# My_CryStal.net
KiCad netlist of a schematic drawn in Altium Designer
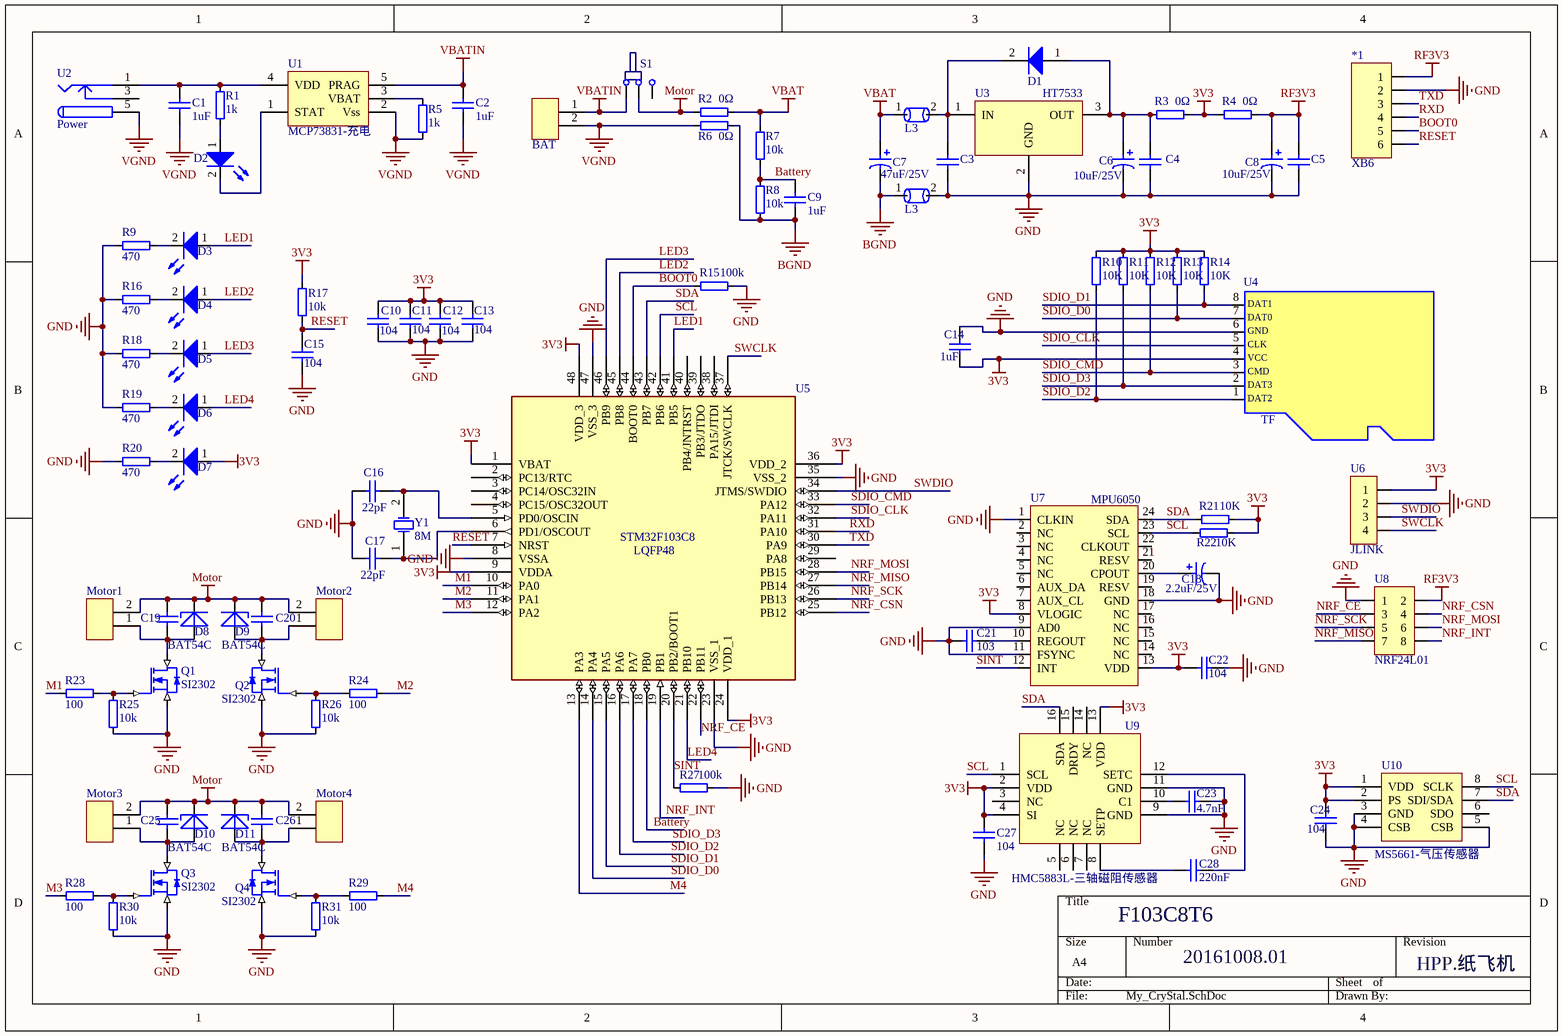
[diagram p0: My_CryStal.SchDoc]

(export (version "E")
  (design (tool "Eeschema 10.0.6"))
  (components
    (comp (ref "*1") (value "XB6") (footprint "SIP6") (libsource (lib "My_Sheet-All_STM32") (part "XB6")))
    (comp (ref "*2") (value "L3") (footprint "2010") (libsource (lib "My_Sheet-All_STM32") (part "L3")))
    (comp (ref "*3") (value "L3") (footprint "2010") (libsource (lib "My_Sheet-All_STM32") (part "L3")))
    (comp (ref "C1")
      (value "1uF")
      (footprint "0805 - duplicate")
      (description "0805")
      (fields (field (name "TOLERANCE") "10%"))
      (libsource (lib "My_Sheet-All_STM32") (part "CAP SMD 0603  X5R 1µF 25V 10%"))
    )
    (comp (ref "C2")
      (value "1uF")
      (footprint "0805 - duplicate")
      (description "0805")
      (fields (field (name "TOLERANCE") "10%"))
      (libsource (lib "My_Sheet-All_STM32") (part "CAP SMD 0603  X5R 1µF 25V 10%"))
    )
    (comp (ref "C3")
      (value "104")
      (footprint "0805 - duplicate")
      (description "0805")
      (fields (field (name "PUBLISHER") "Altium Limited"))
      (libsource (lib "My_Sheet-All_STM32") (part "C1"))
    )
    (comp (ref "C4")
      (value "104")
      (footprint "0805 - duplicate")
      (description "0805")
      (fields (field (name "PUBLISHER") "Altium Limited"))
      (libsource (lib "My_Sheet-All_STM32") (part "C1"))
    )
    (comp (ref "C5")
      (value "104")
      (footprint "0805 - duplicate")
      (description "0805")
      (fields (field (name "PUBLISHER") "Altium Limited"))
      (libsource (lib "My_Sheet-All_STM32") (part "C1"))
    )
    (comp (ref "C6")
      (value "10uF/25V")
      (footprint "1206")
      (description "0805")
      (fields (field (name "PUBLISHER") "Altium Limited"))
      (libsource (lib "My_Sheet-All_STM32") (part "Cap Pol"))
    )
    (comp (ref "C7")
      (value "47uF/25V")
      (footprint "1206")
      (description "0805")
      (fields (field (name "PUBLISHER") "Altium Limited"))
      (libsource (lib "My_Sheet-All_STM32") (part "Cap Pol"))
    )
    (comp (ref "C8")
      (value "10uF/25V")
      (footprint "1206")
      (description "0805")
      (fields (field (name "PUBLISHER") "Altium Limited"))
      (libsource (lib "My_Sheet-All_STM32") (part "Cap Pol"))
    )
    (comp (ref "C9")
      (value "1uF")
      (footprint "0805 - duplicate")
      (description "0805")
      (fields (field (name "TOLERANCE") "10%"))
      (libsource (lib "My_Sheet-All_STM32") (part "CAP SMD 0603  X5R 1µF 25V 10%"))
    )
    (comp (ref "C10")
      (value "104")
      (footprint "0805 - duplicate")
      (description "Cap")
      (fields (field (name "PUBLISHER") "Altium Limited"))
      (libsource (lib "My_Sheet-All_STM32") (part "C1"))
    )
    (comp (ref "C11")
      (value "104")
      (footprint "0805 - duplicate")
      (description "Cap")
      (fields (field (name "PUBLISHER") "Altium Limited"))
      (libsource (lib "My_Sheet-All_STM32") (part "C1"))
    )
    (comp (ref "C12")
      (value "104")
      (footprint "0805 - duplicate")
      (description "Cap")
      (fields (field (name "PUBLISHER") "Altium Limited"))
      (libsource (lib "My_Sheet-All_STM32") (part "C1"))
    )
    (comp (ref "C13")
      (value "104")
      (footprint "0805 - duplicate")
      (description "Cap")
      (fields (field (name "PUBLISHER") "Altium Limited"))
      (libsource (lib "My_Sheet-All_STM32") (part "C1"))
    )
    (comp (ref "C14")
      (value "1uF")
      (footprint "0805 - duplicate")
      (description "0805")
      (fields (field (name "TOLERANCE") "10%"))
      (libsource (lib "My_Sheet-All_STM32") (part "CAP SMD 0603  X5R 1µF 25V 10%"))
    )
    (comp (ref "C15")
      (value "104")
      (footprint "0805 - duplicate")
      (description "Cap")
      (fields (field (name "PUBLISHER") "Altium Limited"))
      (libsource (lib "My_Sheet-All_STM32") (part "C1"))
    )
    (comp (ref "C16")
      (value "22pF")
      (footprint "0805 - duplicate")
      (description "Capacitor")
      (fields (field (name "Comment") "Cap") (field (name "PUBLISHER") "Altium Limited"))
      (libsource (lib "Miscellaneous Devices") (part "Cap"))
    )
    (comp (ref "C17")
      (value "22pF")
      (footprint "0805 - duplicate")
      (description "Capacitor")
      (fields (field (name "Comment") "Cap") (field (name "PUBLISHER") "Altium Limited"))
      (libsource (lib "Miscellaneous Devices") (part "Cap"))
    )
    (comp (ref "C18")
      (value "2.2uF/25V")
      (footprint "1206")
      (description "0805")
      (fields (field (name "PUBLISHER") "Altium Limited"))
      (libsource (lib "") (part "Cap Pol_1"))
    )
    (comp (ref "C19")
      (value "104")
      (footprint "0805 - duplicate")
      (description "Cap")
      (fields (field (name "PUBLISHER") "Altium Limited"))
      (libsource (lib "My_Sheet-All_STM32") (part "C1"))
    )
    (comp (ref "C20")
      (value "104")
      (footprint "0805 - duplicate")
      (description "Cap")
      (fields (field (name "PUBLISHER") "Altium Limited"))
      (libsource (lib "My_Sheet-All_STM32") (part "C1"))
    )
    (comp (ref "C21")
      (value "103")
      (footprint "0805 - duplicate")
      (description "0805")
      (fields (field (name "TOLERANCE") "10%"))
      (libsource (lib "My_Sheet-All_STM32") (part "CAP SMD 0603  X5R 1µF 25V 10%"))
    )
    (comp (ref "C22")
      (value "104")
      (footprint "0805 - duplicate")
      (description "0805")
      (fields (field (name "TOLERANCE") "10%"))
      (libsource (lib "My_Sheet-All_STM32") (part "CAP SMD 0603  X5R 1µF 25V 10%"))
    )
    (comp (ref "C23")
      (value "4.7nF")
      (footprint "0805 - duplicate")
      (description "0805")
      (fields (field (name "TOLERANCE") "10%"))
      (libsource (lib "My_Sheet-All_STM32") (part "CAP SMD 0603  X5R 1µF 25V 10%"))
    )
    (comp (ref "C24")
      (value "104")
      (footprint "0805 - duplicate")
      (description "0805")
      (fields (field (name "TOLERANCE") "10%"))
      (libsource (lib "My_Sheet-All_STM32") (part "CAP SMD 0603  X5R 1µF 25V 10%"))
    )
    (comp (ref "C25")
      (value "104")
      (footprint "0805 - duplicate")
      (description "Cap")
      (fields (field (name "PUBLISHER") "Altium Limited"))
      (libsource (lib "My_Sheet-All_STM32") (part "C1"))
    )
    (comp (ref "C26")
      (value "104")
      (footprint "0805 - duplicate")
      (description "Cap")
      (fields (field (name "PUBLISHER") "Altium Limited"))
      (libsource (lib "My_Sheet-All_STM32") (part "C1"))
    )
    (comp (ref "C27")
      (value "104")
      (footprint "0805 - duplicate")
      (description "0805")
      (fields (field (name "TOLERANCE") "10%"))
      (libsource (lib "My_Sheet-All_STM32") (part "CAP SMD 0603  X5R 1µF 25V 10%"))
    )
    (comp (ref "C28")
      (value "220nF")
      (footprint "0805 - duplicate")
      (description "0805")
      (fields (field (name "TOLERANCE") "10%"))
      (libsource (lib "My_Sheet-All_STM32") (part "CAP SMD 0603  X5R 1µF 25V 10%"))
    )
    (comp (ref "CON1") (value "BAT") (footprint "SIP2") (libsource (lib "") (part "CON2_2")))
    (comp (ref "CON2")
      (value "Motor1")
      (footprint "SIP2")
      (libsource (lib "My_Sheet-All_STM32") (part "CON2"))
    )
    (comp (ref "CON3") (value "Motor2") (footprint "SIP2") (libsource (lib "") (part "CON2_1")))
    (comp (ref "CON4")
      (value "Motor3")
      (footprint "SIP2")
      (libsource (lib "My_Sheet-All_STM32") (part "CON2"))
    )
    (comp (ref "CON5") (value "Motor4") (footprint "SIP2") (libsource (lib "") (part "CON2_1")))
    (comp (ref "D1")
      (value "Diode")
      (footprint "DIODE-SMB")
      (description "整流二极管")
      (fields (field (name "PUBLISHER") "Altium Limited"))
      (libsource (lib "My_Sheet-All_STM32") (part "Diode"))
    )
    (comp (ref "D2")
      (value "LED")
      (footprint "LED")
      (description "发光二极管")
      (fields (field (name "PUBLISHER") "Altium Limited"))
      (libsource (lib "My_Sheet-All_STM32") (part "LED"))
    )
    (comp (ref "D3")
      (value "LED")
      (footprint "LED")
      (description "发光二极管")
      (fields (field (name "PUBLISHER") "Altium Limited"))
      (libsource (lib "My_Sheet-All_STM32") (part "LED"))
    )
    (comp (ref "D4")
      (value "LED")
      (footprint "LED")
      (description "发光二极管")
      (fields (field (name "PUBLISHER") "Altium Limited"))
      (libsource (lib "My_Sheet-All_STM32") (part "LED"))
    )
    (comp (ref "D5")
      (value "LED")
      (footprint "LED")
      (description "发光二极管")
      (fields (field (name "PUBLISHER") "Altium Limited"))
      (libsource (lib "My_Sheet-All_STM32") (part "LED"))
    )
    (comp (ref "D6")
      (value "LED")
      (footprint "LED")
      (description "发光二极管")
      (fields (field (name "PUBLISHER") "Altium Limited"))
      (libsource (lib "My_Sheet-All_STM32") (part "LED"))
    )
    (comp (ref "D7")
      (value "LED")
      (footprint "LED")
      (description "发光二极管")
      (fields (field (name "PUBLISHER") "Altium Limited"))
      (libsource (lib "My_Sheet-All_STM32") (part "LED"))
    )
    (comp (ref "D8")
      (value "BAT54C")
      (footprint "DIODE-SMB")
      (libsource (lib "My_Sheet-All_STM32") (part "TVS"))
    )
    (comp (ref "D9")
      (value "BAT54C")
      (footprint "DIODE-SMB")
      (libsource (lib "My_Sheet-All_STM32") (part "TVS"))
    )
    (comp (ref "D10")
      (value "BAT54C")
      (footprint "DIODE-SMB")
      (libsource (lib "My_Sheet-All_STM32") (part "TVS"))
    )
    (comp (ref "D11")
      (value "BAT54C")
      (footprint "DIODE-SMB")
      (libsource (lib "My_Sheet-All_STM32") (part "TVS"))
    )
    (comp (ref "Q1")
      (value "SI2302")
      (footprint "SOT-23")
      (description "N-Channel MOSFET")
      (libsource (lib "My_Sheet-All_STM32") (part "IRF740"))
    )
    (comp (ref "Q2")
      (value "SI2302")
      (footprint "SOT-23")
      (description "N-Channel MOSFET")
      (libsource (lib "My_Sheet-All_STM32") (part "IRF740"))
    )
    (comp (ref "Q3")
      (value "SI2302")
      (footprint "SOT-23")
      (description "N-Channel MOSFET")
      (libsource (lib "My_Sheet-All_STM32") (part "IRF740"))
    )
    (comp (ref "Q4")
      (value "SI2302")
      (footprint "SOT-23")
      (description "N-Channel MOSFET")
      (libsource (lib "My_Sheet-All_STM32") (part "IRF740"))
    )
    (comp (ref "R1")
      (value "1k")
      (footprint "0805 - duplicate")
      (libsource (lib "My_Sheet-All_STM32") (part "RES_1"))
    )
    (comp (ref "R2")
      (value "0Ω")
      (footprint "0805 - duplicate")
      (libsource (lib "My_Sheet-All_STM32") (part "RES_1"))
    )
    (comp (ref "R3")
      (value "0Ω")
      (footprint "0805 - duplicate")
      (libsource (lib "My_Sheet-All_STM32") (part "RES_1"))
    )
    (comp (ref "R4")
      (value "0Ω")
      (footprint "0805 - duplicate")
      (libsource (lib "My_Sheet-All_STM32") (part "RES_1"))
    )
    (comp (ref "R5")
      (value "1k")
      (footprint "0805 - duplicate")
      (libsource (lib "My_Sheet-All_STM32") (part "RES_1"))
    )
    (comp (ref "R6")
      (value "0Ω")
      (footprint "0805 - duplicate")
      (libsource (lib "My_Sheet-All_STM32") (part "RES_1"))
    )
    (comp (ref "R7")
      (value "10k")
      (footprint "0805 - duplicate")
      (libsource (lib "My_Sheet-All_STM32") (part "RES_1"))
    )
    (comp (ref "R8")
      (value "10k")
      (footprint "0805 - duplicate")
      (libsource (lib "My_Sheet-All_STM32") (part "RES_1"))
    )
    (comp (ref "R9")
      (value "470")
      (footprint "0805 - duplicate")
      (libsource (lib "My_Sheet-All_STM32") (part "RES_1"))
    )
    (comp (ref "R10")
      (value "10K")
      (footprint "0805 - duplicate")
      (libsource (lib "My_Sheet-All_STM32") (part "RES_1"))
    )
    (comp (ref "R11")
      (value "10K")
      (footprint "0805 - duplicate")
      (libsource (lib "My_Sheet-All_STM32") (part "RES_1"))
    )
    (comp (ref "R12")
      (value "10K")
      (footprint "0805 - duplicate")
      (libsource (lib "My_Sheet-All_STM32") (part "RES_1"))
    )
    (comp (ref "R13")
      (value "10K")
      (footprint "0805 - duplicate")
      (libsource (lib "My_Sheet-All_STM32") (part "RES_1"))
    )
    (comp (ref "R14")
      (value "10K")
      (footprint "0805 - duplicate")
      (libsource (lib "My_Sheet-All_STM32") (part "RES_1"))
    )
    (comp (ref "R15")
      (value "100k")
      (footprint "0805 - duplicate")
      (libsource (lib "My_Sheet-All_STM32") (part "RES_1"))
    )
    (comp (ref "R16")
      (value "470")
      (footprint "0805 - duplicate")
      (libsource (lib "My_Sheet-All_STM32") (part "RES_1"))
    )
    (comp (ref "R17")
      (value "10k")
      (footprint "0805 - duplicate")
      (libsource (lib "My_Sheet-All_STM32") (part "RES_1"))
    )
    (comp (ref "R18")
      (value "470")
      (footprint "0805 - duplicate")
      (libsource (lib "My_Sheet-All_STM32") (part "RES_1"))
    )
    (comp (ref "R19")
      (value "470")
      (footprint "0805 - duplicate")
      (libsource (lib "My_Sheet-All_STM32") (part "RES_1"))
    )
    (comp (ref "R20")
      (value "470")
      (footprint "0805 - duplicate")
      (libsource (lib "My_Sheet-All_STM32") (part "RES_1"))
    )
    (comp (ref "R21")
      (value "10K")
      (footprint "0805 - duplicate")
      (libsource (lib "My_Sheet-All_STM32") (part "RES_1"))
    )
    (comp (ref "R22")
      (value "10K")
      (footprint "0805 - duplicate")
      (libsource (lib "My_Sheet-All_STM32") (part "RES_1"))
    )
    (comp (ref "R23")
      (value "100")
      (footprint "0805 - duplicate")
      (libsource (lib "My_Sheet-All_STM32") (part "RES_1"))
    )
    (comp (ref "R24")
      (value "100")
      (footprint "0805 - duplicate")
      (libsource (lib "My_Sheet-All_STM32") (part "RES_1"))
    )
    (comp (ref "R25")
      (value "10k")
      (footprint "0805 - duplicate")
      (libsource (lib "My_Sheet-All_STM32") (part "RES_1"))
    )
    (comp (ref "R26")
      (value "10k")
      (footprint "0805 - duplicate")
      (libsource (lib "My_Sheet-All_STM32") (part "RES_1"))
    )
    (comp (ref "R27")
      (value "100k")
      (footprint "0805 - duplicate")
      (libsource (lib "My_Sheet-All_STM32") (part "RES_1"))
    )
    (comp (ref "R28")
      (value "100")
      (footprint "0805 - duplicate")
      (libsource (lib "My_Sheet-All_STM32") (part "RES_1"))
    )
    (comp (ref "R29")
      (value "100")
      (footprint "0805 - duplicate")
      (libsource (lib "My_Sheet-All_STM32") (part "RES_1"))
    )
    (comp (ref "R30")
      (value "10k")
      (footprint "0805 - duplicate")
      (libsource (lib "My_Sheet-All_STM32") (part "RES_1"))
    )
    (comp (ref "R31")
      (value "10k")
      (footprint "0805 - duplicate")
      (libsource (lib "My_Sheet-All_STM32") (part "RES_1"))
    )
    (comp (ref "S1") (value "SW") (footprint "SWITCH_B1") (libsource (lib "My_Sheet-All_STM32") (part "SW")))
    (comp (ref "U1")
      (value "MCP73831-充电")
      (footprint "SOT23-5")
      (libsource (lib "My_Sheet-All_STM32") (part "MCP73831"))
    )
    (comp (ref "U2") (value "Power") (footprint "USB5") (libsource (lib "My_Sheet-All_STM32") (part "Power")))
    (comp (ref "U3")
      (value "HT7533")
      (footprint "SOT-89")
      (libsource (lib "My_Sheet-All_STM32") (part "HT7533"))
    )
    (comp (ref "U4") (value "TF") (footprint "SDCARD_L") (libsource (lib "My_Sheet-All_STM32") (part "TF")))
    (comp (ref "U5")
      (value "STM32F103C8T6-1")
      (footprint "LQFP48S")
      (description "Medium-density performance line ARM-based 32-bit MCU with 64KB Flash, USB, CAN, 7 timers, 2 ADCs")
      (libsource (lib "My_Sheet-All_STM32") (part "STM32F103C8T6-1"))
    )
    (comp (ref "U6") (value "JLINK") (footprint "SIP4") (libsource (lib "My_Sheet-All_STM32") (part "X4")))
    (comp (ref "U7")
      (value "MPU6050")
      (footprint "QFN24")
      (libsource (lib "My_Sheet-All_STM32") (part "MPU6050"))
    )
    (comp (ref "U8")
      (value "NRF24L01")
      (footprint "DIP8")
      (description "Header, 6-Pin")
      (fields (field (name "PUBLISHER") "*"))
      (libsource (lib "My_Sheet-All_STM32") (part "Header 4X2"))
    )
    (comp (ref "U9")
      (value "HMC5883L-三轴磁阻传感器")
      (footprint "LCC16")
      (libsource (lib "My_Sheet-All_STM32") (part "HMC5883L"))
    )
    (comp (ref "U10")
      (value "MS5661-气压传感器")
      (footprint "LCC8")
      (libsource (lib "My_Sheet-All_STM32") (part "MS5611"))
    )
    (comp (ref "Y1")
      (value "8M")
      (footprint "XTAL")
      (description "Crystal Oscillator")
      (fields (field (name "PUBLISHER") "Altium Limited"))
      (libsource (lib "Miscellaneous Devices") (part "XTAL"))
    )
  )
  (nets
    (net (code "1") (name "/BOOT0") (class "Default")
      (node (ref "*1") (pin "5") (pinfunction "5_5") (pintype "passive"))
      (node (ref "R15") (pin "2") (pinfunction "2_2") (pintype "passive"))
      (node (ref "U5") (pin "44") (pinfunction "BOOT0_44") (pintype "bidirectional"))
    )
    (net (code "2") (name "/Battery") (class "Default")
      (node (ref "C9") (pin "2") (pinfunction "2_2") (pintype "passive"))
      (node (ref "R7") (pin "1") (pinfunction "1_1") (pintype "passive"))
      (node (ref "R8") (pin "2") (pinfunction "2_2") (pintype "passive"))
      (node (ref "U5") (pin "18") (pinfunction "PB0_18") (pintype "bidirectional"))
    )
    (net (code "3") (name "/LED1") (class "Default")
      (node (ref "D3") (pin "1") (pinfunction "A_1") (pintype "passive"))
      (node (ref "U5") (pin "41") (pinfunction "PB5_41") (pintype "bidirectional"))
    )
    (net (code "4") (name "/LED2") (class "Default")
      (node (ref "D4") (pin "1") (pinfunction "A_1") (pintype "passive"))
      (node (ref "U5") (pin "45") (pinfunction "PB8_45") (pintype "bidirectional"))
    )
    (net (code "5") (name "/LED3") (class "Default")
      (node (ref "D5") (pin "1") (pinfunction "A_1") (pintype "passive"))
      (node (ref "U5") (pin "46") (pinfunction "PB9_46") (pintype "bidirectional"))
    )
    (net (code "6") (name "/LED4") (class "Default")
      (node (ref "D6") (pin "1") (pinfunction "A_1") (pintype "passive"))
      (node (ref "U5") (pin "21") (pinfunction "PB10_21") (pintype "bidirectional"))
    )
    (net (code "7") (name "/M1") (class "Default")
      (node (ref "R23") (pin "1") (pinfunction "1_1") (pintype "passive"))
      (node (ref "U5") (pin "10") (pinfunction "PA0_10") (pintype "bidirectional"))
    )
    (net (code "8") (name "/M2") (class "Default")
      (node (ref "R24") (pin "1") (pinfunction "1_1") (pintype "passive"))
      (node (ref "U5") (pin "11") (pinfunction "PA1_11") (pintype "bidirectional"))
    )
    (net (code "9") (name "/M3") (class "Default")
      (node (ref "R28") (pin "1") (pinfunction "1_1") (pintype "passive"))
      (node (ref "U5") (pin "12") (pinfunction "PA2_12") (pintype "bidirectional"))
    )
    (net (code "10") (name "/M4") (class "Default")
      (node (ref "R29") (pin "1") (pinfunction "1_1") (pintype "passive"))
      (node (ref "U5") (pin "13") (pinfunction "PA3_13") (pintype "bidirectional"))
    )
    (net (code "11") (name "/NRF_CE") (class "Default")
      (node (ref "U5") (pin "22") (pinfunction "PB11_22") (pintype "bidirectional"))
      (node (ref "U8") (pin "3") (pinfunction "3_3") (pintype "passive"))
    )
    (net (code "12") (name "/NRF_CSN") (class "Default")
      (node (ref "U5") (pin "25") (pinfunction "PB12_25") (pintype "bidirectional"))
      (node (ref "U8") (pin "4") (pinfunction "4_4") (pintype "passive"))
    )
    (net (code "13") (name "/NRF_INT") (class "Default")
      (node (ref "U5") (pin "19") (pinfunction "PB1_19") (pintype "input"))
      (node (ref "U8") (pin "8") (pinfunction "8_8") (pintype "passive"))
    )
    (net (code "14") (name "/NRF_MISO") (class "Default")
      (node (ref "U5") (pin "27") (pinfunction "PB14_27") (pintype "bidirectional"))
      (node (ref "U8") (pin "7") (pinfunction "7_7") (pintype "passive"))
    )
    (net (code "15") (name "/NRF_MOSI") (class "Default")
      (node (ref "U5") (pin "28") (pinfunction "PB15_28") (pintype "bidirectional"))
      (node (ref "U8") (pin "6") (pinfunction "6_6") (pintype "passive"))
    )
    (net (code "16") (name "/NRF_SCK") (class "Default")
      (node (ref "U5") (pin "26") (pinfunction "PB13_26") (pintype "bidirectional"))
      (node (ref "U8") (pin "5") (pinfunction "5_5") (pintype "passive"))
    )
    (net (code "17") (name "/RESET") (class "Default")
      (node (ref "*1") (pin "6") (pinfunction "6_6") (pintype "passive"))
      (node (ref "C15") (pin "2") (pinfunction "2_2") (pintype "passive"))
      (node (ref "R17") (pin "1") (pinfunction "1_1") (pintype "passive"))
      (node (ref "U5") (pin "7") (pinfunction "NRST_7") (pintype "input"))
    )
    (net (code "18") (name "/RXD") (class "Default")
      (node (ref "*1") (pin "4") (pinfunction "4_4") (pintype "passive"))
      (node (ref "U5") (pin "31") (pinfunction "PA10_31") (pintype "bidirectional"))
    )
    (net (code "19") (name "/SCL") (class "Default")
      (node (ref "R22") (pin "2") (pinfunction "2_2") (pintype "passive"))
      (node (ref "U10") (pin "8") (pinfunction "SCLK_8") (pintype "passive"))
      (node (ref "U5") (pin "42") (pinfunction "PB6_42") (pintype "bidirectional"))
      (node (ref "U7") (pin "23") (pinfunction "SCL_23") (pintype "passive"))
      (node (ref "U9") (pin "1") (pinfunction "SCL_1") (pintype "passive"))
    )
    (net (code "20") (name "/SDA") (class "Default")
      (node (ref "R21") (pin "2") (pinfunction "2_2") (pintype "passive"))
      (node (ref "U10") (pin "7") (pinfunction "SDI/SDA_7") (pintype "passive"))
      (node (ref "U5") (pin "43") (pinfunction "PB7_43") (pintype "bidirectional"))
      (node (ref "U7") (pin "24") (pinfunction "SDA_24") (pintype "passive"))
      (node (ref "U9") (pin "16") (pinfunction "SDA_16") (pintype "passive"))
    )
    (net (code "21") (name "/SDIO_CLK") (class "Default")
      (node (ref "U4") (pin "5") (pinfunction "5_5") (pintype "passive"))
      (node (ref "U5") (pin "32") (pinfunction "PA11_32") (pintype "bidirectional"))
    )
    (net (code "22") (name "/SDIO_CMD") (class "Default")
      (node (ref "R12") (pin "2") (pinfunction "2_2") (pintype "passive"))
      (node (ref "U4") (pin "3") (pinfunction "3_3") (pintype "passive"))
      (node (ref "U5") (pin "33") (pinfunction "PA12_33") (pintype "bidirectional"))
    )
    (net (code "23") (name "/SDIO_D0") (class "Default")
      (node (ref "R13") (pin "2") (pinfunction "2_2") (pintype "passive"))
      (node (ref "U4") (pin "7") (pinfunction "7_7") (pintype "passive"))
      (node (ref "U5") (pin "14") (pinfunction "PA4_14") (pintype "bidirectional"))
    )
    (net (code "24") (name "/SDIO_D1") (class "Default")
      (node (ref "R14") (pin "2") (pinfunction "2_2") (pintype "passive"))
      (node (ref "U4") (pin "8") (pinfunction "8_8") (pintype "passive"))
      (node (ref "U5") (pin "15") (pinfunction "PA5_15") (pintype "bidirectional"))
    )
    (net (code "25") (name "/SDIO_D2") (class "Default")
      (node (ref "R10") (pin "2") (pinfunction "2_2") (pintype "passive"))
      (node (ref "U4") (pin "1") (pinfunction "1_1") (pintype "passive"))
      (node (ref "U5") (pin "16") (pinfunction "PA6_16") (pintype "bidirectional"))
    )
    (net (code "26") (name "/SDIO_D3") (class "Default")
      (node (ref "R11") (pin "2") (pinfunction "2_2") (pintype "passive"))
      (node (ref "U4") (pin "2") (pinfunction "2_2") (pintype "passive"))
      (node (ref "U5") (pin "17") (pinfunction "PA7_17") (pintype "bidirectional"))
    )
    (net (code "27") (name "/SINT") (class "Default")
      (node (ref "R27") (pin "2") (pinfunction "2_2") (pintype "passive"))
      (node (ref "U5") (pin "20") (pinfunction "PB2/BOOT1_20") (pintype "bidirectional"))
      (node (ref "U7") (pin "12") (pinfunction "INT_12") (pintype "passive"))
    )
    (net (code "28") (name "/SWCLK") (class "Default")
      (node (ref "U5") (pin "37") (pinfunction "JTCK/SWCLK_37") (pintype "bidirectional"))
      (node (ref "U6") (pin "4") (pinfunction "4_4") (pintype "passive"))
    )
    (net (code "29") (name "/SWDIO") (class "Default")
      (node (ref "U5") (pin "34") (pinfunction "JTMS/SWDIO_34") (pintype "bidirectional"))
      (node (ref "U6") (pin "3") (pinfunction "3_3") (pintype "passive"))
    )
    (net (code "30") (name "/TXD") (class "Default")
      (node (ref "*1") (pin "3") (pinfunction "3_3") (pintype "passive"))
      (node (ref "U5") (pin "30") (pinfunction "PA9_30") (pintype "bidirectional"))
    )
    (net (code "31") (name "3V3") (class "Default")
      (node (ref "C10") (pin "2") (pinfunction "2_2") (pintype "passive"))
      (node (ref "C11") (pin "2") (pinfunction "2_2") (pintype "passive"))
      (node (ref "C12") (pin "2") (pinfunction "2_2") (pintype "passive"))
      (node (ref "C13") (pin "2") (pinfunction "2_2") (pintype "passive"))
      (node (ref "C14") (pin "1") (pinfunction "1_1") (pintype "passive"))
      (node (ref "C22") (pin "1") (pinfunction "1_1") (pintype "passive"))
      (node (ref "C24") (pin "1") (pinfunction "1_1") (pintype "passive"))
      (node (ref "C27") (pin "1") (pinfunction "1_1") (pintype "passive"))
      (node (ref "D7") (pin "1") (pinfunction "A_1") (pintype "passive"))
      (node (ref "R10") (pin "1") (pinfunction "1_1") (pintype "passive"))
      (node (ref "R11") (pin "1") (pinfunction "1_1") (pintype "passive"))
      (node (ref "R12") (pin "1") (pinfunction "1_1") (pintype "passive"))
      (node (ref "R13") (pin "1") (pinfunction "1_1") (pintype "passive"))
      (node (ref "R14") (pin "1") (pinfunction "1_1") (pintype "passive"))
      (node (ref "R17") (pin "2") (pinfunction "2_2") (pintype "passive"))
      (node (ref "R21") (pin "1") (pinfunction "1_1") (pintype "passive"))
      (node (ref "R22") (pin "1") (pinfunction "1_1") (pintype "passive"))
      (node (ref "R3") (pin "1") (pinfunction "1_1") (pintype "passive"))
      (node (ref "R4") (pin "2") (pinfunction "2_2") (pintype "passive"))
      (node (ref "U10") (pin "1") (pinfunction "VDD_1") (pintype "passive"))
      (node (ref "U10") (pin "2") (pinfunction "PS_2") (pintype "passive"))
      (node (ref "U4") (pin "4") (pinfunction "4_4") (pintype "passive"))
      (node (ref "U5") (pin "1") (pinfunction "VBAT_1") (pintype "power_in"))
      (node (ref "U5") (pin "24") (pinfunction "VDD_1_24") (pintype "power_in"))
      (node (ref "U5") (pin "36") (pinfunction "VDD_2_36") (pintype "power_in"))
      (node (ref "U5") (pin "48") (pinfunction "VDD_3_48") (pintype "power_in"))
      (node (ref "U5") (pin "9") (pinfunction "VDDA_9") (pintype "power_in"))
      (node (ref "U6") (pin "1") (pinfunction "1_1") (pintype "passive"))
      (node (ref "U7") (pin "13") (pinfunction "VDD_13") (pintype "passive"))
      (node (ref "U7") (pin "8") (pinfunction "VLOGIC_8") (pintype "passive"))
      (node (ref "U9") (pin "13") (pinfunction "VDD_13") (pintype "passive"))
      (node (ref "U9") (pin "2") (pinfunction "VDD_2") (pintype "passive"))
      (node (ref "U9") (pin "4") (pinfunction "SI_4") (pintype "passive"))
    )
    (net (code "32") (name "BGND") (class "Default")
      (node (ref "*3") (pin "1") (pinfunction "1_1") (pintype "passive"))
      (node (ref "C7") (pin "2") (pinfunction "2_2") (pintype "passive"))
      (node (ref "C9") (pin "1") (pinfunction "1_1") (pintype "passive"))
      (node (ref "R6") (pin "2") (pinfunction "2_2") (pintype "passive"))
      (node (ref "R8") (pin "1") (pinfunction "1_1") (pintype "passive"))
    )
    (net (code "33") (name "GND") (class "Default")
      (node (ref "*1") (pin "2") (pinfunction "2_2") (pintype "passive"))
      (node (ref "*3") (pin "2") (pinfunction "2_2") (pintype "passive"))
      (node (ref "C10") (pin "1") (pinfunction "1_1") (pintype "passive"))
      (node (ref "C11") (pin "1") (pinfunction "1_1") (pintype "passive"))
      (node (ref "C12") (pin "1") (pinfunction "1_1") (pintype "passive"))
      (node (ref "C13") (pin "1") (pinfunction "1_1") (pintype "passive"))
      (node (ref "C14") (pin "2") (pinfunction "2_2") (pintype "passive"))
      (node (ref "C15") (pin "1") (pinfunction "1_1") (pintype "passive"))
      (node (ref "C16") (pin "1") (pinfunction "1_1") (pintype "passive"))
      (node (ref "C17") (pin "1") (pinfunction "1_1") (pintype "passive"))
      (node (ref "C18") (pin "2") (pinfunction "2_2") (pintype "passive"))
      (node (ref "C21") (pin "2") (pinfunction "2_2") (pintype "passive"))
      (node (ref "C22") (pin "2") (pinfunction "2_2") (pintype "passive"))
      (node (ref "C23") (pin "2") (pinfunction "2_2") (pintype "passive"))
      (node (ref "C24") (pin "2") (pinfunction "2_2") (pintype "passive"))
      (node (ref "C27") (pin "2") (pinfunction "2_2") (pintype "passive"))
      (node (ref "C3") (pin "1") (pinfunction "1_1") (pintype "passive"))
      (node (ref "C4") (pin "1") (pinfunction "1_1") (pintype "passive"))
      (node (ref "C5") (pin "1") (pinfunction "1_1") (pintype "passive"))
      (node (ref "C6") (pin "2") (pinfunction "2_2") (pintype "passive"))
      (node (ref "C8") (pin "2") (pinfunction "2_2") (pintype "passive"))
      (node (ref "Q1") (pin "3") (pinfunction "S_3") (pintype "input"))
      (node (ref "Q2") (pin "3") (pinfunction "S_3") (pintype "input"))
      (node (ref "Q3") (pin "3") (pinfunction "S_3") (pintype "input"))
      (node (ref "Q4") (pin "3") (pinfunction "S_3") (pintype "input"))
      (node (ref "R15") (pin "1") (pinfunction "1_1") (pintype "passive"))
      (node (ref "R16") (pin "1") (pinfunction "1_1") (pintype "passive"))
      (node (ref "R18") (pin "1") (pinfunction "1_1") (pintype "passive"))
      (node (ref "R19") (pin "1") (pinfunction "1_1") (pintype "passive"))
      (node (ref "R20") (pin "1") (pinfunction "1_1") (pintype "passive"))
      (node (ref "R25") (pin "1") (pinfunction "1_1") (pintype "passive"))
      (node (ref "R26") (pin "1") (pinfunction "1_1") (pintype "passive"))
      (node (ref "R27") (pin "1") (pinfunction "1_1") (pintype "passive"))
      (node (ref "R30") (pin "1") (pinfunction "1_1") (pintype "passive"))
      (node (ref "R31") (pin "1") (pinfunction "1_1") (pintype "passive"))
      (node (ref "R9") (pin "1") (pinfunction "1_1") (pintype "passive"))
      (node (ref "U10") (pin "3") (pinfunction "GND_3") (pintype "passive"))
      (node (ref "U10") (pin "4") (pinfunction "CSB_4") (pintype "passive"))
      (node (ref "U10") (pin "5") (pinfunction "CSB_5") (pintype "passive"))
      (node (ref "U3") (pin "2") (pinfunction "GND_2") (pintype "passive"))
      (node (ref "U4") (pin "6") (pinfunction "6_6") (pintype "passive"))
      (node (ref "U5") (pin "23") (pinfunction "VSS_1_23") (pintype "power_in"))
      (node (ref "U5") (pin "35") (pinfunction "VSS_2_35") (pintype "power_in"))
      (node (ref "U5") (pin "47") (pinfunction "VSS_3_47") (pintype "power_in"))
      (node (ref "U5") (pin "8") (pinfunction "VSSA_8") (pintype "power_in"))
      (node (ref "U6") (pin "2") (pinfunction "2_2") (pintype "passive"))
      (node (ref "U7") (pin "1") (pinfunction "CLKIN_1") (pintype "passive"))
      (node (ref "U7") (pin "11") (pinfunction "FSYNC_11") (pintype "passive"))
      (node (ref "U7") (pin "18") (pinfunction "GND_18") (pintype "passive"))
      (node (ref "U7") (pin "9") (pinfunction "AD0_9") (pintype "passive"))
      (node (ref "U8") (pin "1") (pinfunction "1_1") (pintype "passive"))
      (node (ref "U9") (pin "11") (pinfunction "GND_11") (pintype "passive"))
      (node (ref "U9") (pin "9") (pinfunction "GND_9") (pintype "passive"))
    )
    (net (code "34") (name "Motor") (class "Default")
      (node (ref "C19") (pin "2") (pinfunction "2_2") (pintype "passive"))
      (node (ref "C20") (pin "2") (pinfunction "2_2") (pintype "passive"))
      (node (ref "C25") (pin "2") (pinfunction "2_2") (pintype "passive"))
      (node (ref "C26") (pin "2") (pinfunction "2_2") (pintype "passive"))
      (node (ref "CON2") (pin "2") (pinfunction "2_2") (pintype "passive"))
      (node (ref "CON3") (pin "2") (pinfunction "2_2") (pintype "passive"))
      (node (ref "CON4") (pin "2") (pinfunction "2_2") (pintype "passive"))
      (node (ref "CON5") (pin "2") (pinfunction "2_2") (pintype "passive"))
      (node (ref "D10") (pin "2") (pinfunction "K_2") (pintype "passive"))
      (node (ref "D11") (pin "2") (pinfunction "K_2") (pintype "passive"))
      (node (ref "D8") (pin "2") (pinfunction "K_2") (pintype "passive"))
      (node (ref "D9") (pin "2") (pinfunction "K_2") (pintype "passive"))
      (node (ref "R2") (pin "2") (pinfunction "2_2") (pintype "passive"))
      (node (ref "S1") (pin "2") (pinfunction "2_2") (pintype "passive"))
    )
    (net (code "35") (name "Net-(D2-A)") (class "Default")
      (node (ref "D2") (pin "1") (pinfunction "A_1") (pintype "passive"))
      (node (ref "R1") (pin "1") (pinfunction "1_1") (pintype "passive"))
    )
    (net (code "36") (name "Net-(D2-K)") (class "Default")
      (node (ref "D2") (pin "2") (pinfunction "K_2") (pintype "passive"))
      (node (ref "U1") (pin "1") (pinfunction "STAT_1") (pintype "passive"))
    )
    (net (code "37") (name "Net-(D3-K)") (class "Default")
      (node (ref "D3") (pin "2") (pinfunction "K_2") (pintype "passive"))
      (node (ref "R9") (pin "2") (pinfunction "2_2") (pintype "passive"))
    )
    (net (code "38") (name "Net-(D4-K)") (class "Default")
      (node (ref "D4") (pin "2") (pinfunction "K_2") (pintype "passive"))
      (node (ref "R16") (pin "2") (pinfunction "2_2") (pintype "passive"))
    )
    (net (code "39") (name "Net-(D5-K)") (class "Default")
      (node (ref "D5") (pin "2") (pinfunction "K_2") (pintype "passive"))
      (node (ref "R18") (pin "2") (pinfunction "2_2") (pintype "passive"))
    )
    (net (code "40") (name "Net-(D6-K)") (class "Default")
      (node (ref "D6") (pin "2") (pinfunction "K_2") (pintype "passive"))
      (node (ref "R19") (pin "2") (pinfunction "2_2") (pintype "passive"))
    )
    (net (code "41") (name "Net-(D7-K)") (class "Default")
      (node (ref "D7") (pin "2") (pinfunction "K_2") (pintype "passive"))
      (node (ref "R20") (pin "2") (pinfunction "2_2") (pintype "passive"))
    )
    (net (code "42") (name "Net-(D8-A)") (class "Default")
      (node (ref "C19") (pin "1") (pinfunction "1_1") (pintype "passive"))
      (node (ref "CON2") (pin "1") (pinfunction "1_1") (pintype "passive"))
      (node (ref "D8") (pin "1") (pinfunction "A_1") (pintype "passive"))
      (node (ref "Q1") (pin "2") (pinfunction "D_2") (pintype "input"))
    )
    (net (code "43") (name "Net-(D9-A)") (class "Default")
      (node (ref "C20") (pin "1") (pinfunction "1_1") (pintype "passive"))
      (node (ref "CON3") (pin "1") (pinfunction "1_1") (pintype "passive"))
      (node (ref "D9") (pin "1") (pinfunction "A_1") (pintype "passive"))
      (node (ref "Q2") (pin "2") (pinfunction "D_2") (pintype "input"))
    )
    (net (code "44") (name "Net-(D10-A)") (class "Default")
      (node (ref "C25") (pin "1") (pinfunction "1_1") (pintype "passive"))
      (node (ref "CON4") (pin "1") (pinfunction "1_1") (pintype "passive"))
      (node (ref "D10") (pin "1") (pinfunction "A_1") (pintype "passive"))
      (node (ref "Q3") (pin "2") (pinfunction "D_2") (pintype "input"))
    )
    (net (code "45") (name "Net-(D11-A)") (class "Default")
      (node (ref "C26") (pin "1") (pinfunction "1_1") (pintype "passive"))
      (node (ref "CON5") (pin "1") (pinfunction "1_1") (pintype "passive"))
      (node (ref "D11") (pin "1") (pinfunction "A_1") (pintype "passive"))
      (node (ref "Q4") (pin "2") (pinfunction "D_2") (pintype "input"))
    )
    (net (code "46") (name "Net-(Q1-G)") (class "Default")
      (node (ref "Q1") (pin "1") (pinfunction "G_1") (pintype "input"))
      (node (ref "R23") (pin "2") (pinfunction "2_2") (pintype "passive"))
      (node (ref "R25") (pin "2") (pinfunction "2_2") (pintype "passive"))
    )
    (net (code "47") (name "Net-(Q2-G)") (class "Default")
      (node (ref "Q2") (pin "1") (pinfunction "G_1") (pintype "input"))
      (node (ref "R24") (pin "2") (pinfunction "2_2") (pintype "passive"))
      (node (ref "R26") (pin "2") (pinfunction "2_2") (pintype "passive"))
    )
    (net (code "48") (name "Net-(Q3-G)") (class "Default")
      (node (ref "Q3") (pin "1") (pinfunction "G_1") (pintype "input"))
      (node (ref "R28") (pin "2") (pinfunction "2_2") (pintype "passive"))
      (node (ref "R30") (pin "2") (pinfunction "2_2") (pintype "passive"))
    )
    (net (code "49") (name "Net-(Q4-G)") (class "Default")
      (node (ref "Q4") (pin "1") (pinfunction "G_1") (pintype "input"))
      (node (ref "R29") (pin "2") (pinfunction "2_2") (pintype "passive"))
      (node (ref "R31") (pin "2") (pinfunction "2_2") (pintype "passive"))
    )
    (net (code "50") (name "Net-(U1-VBAT)") (class "Default")
      (node (ref "R5") (pin "2") (pinfunction "2_2") (pintype "passive"))
      (node (ref "U1") (pin "3") (pinfunction "VBAT_3") (pintype "passive"))
    )
    (net (code "51") (name "Net-(U1-VDD)") (class "Default")
      (node (ref "C1") (pin "2") (pinfunction "2_2") (pintype "passive"))
      (node (ref "R1") (pin "2") (pinfunction "2_2") (pintype "passive"))
      (node (ref "U1") (pin "4") (pinfunction "VDD_4") (pintype "passive"))
      (node (ref "U2") (pin "1") (pinfunction "1_1") (pintype "power_in"))
    )
    (net (code "52") (name "Net-(U3-IN)") (class "Default")
      (node (ref "*2") (pin "2") (pinfunction "2_2") (pintype "passive"))
      (node (ref "C3") (pin "2") (pinfunction "2_2") (pintype "passive"))
      (node (ref "D1") (pin "2") (pinfunction "2_2") (pintype "passive"))
      (node (ref "U3") (pin "1") (pinfunction "IN_1") (pintype "passive"))
    )
    (net (code "53") (name "Net-(U3-OUT)") (class "Default")
      (node (ref "C4") (pin "2") (pinfunction "2_2") (pintype "passive"))
      (node (ref "C6") (pin "1") (pinfunction "1_1") (pintype "passive"))
      (node (ref "D1") (pin "1") (pinfunction "1_1") (pintype "passive"))
      (node (ref "R3") (pin "2") (pinfunction "2_2") (pintype "passive"))
      (node (ref "U3") (pin "3") (pinfunction "OUT_3") (pintype "passive"))
    )
    (net (code "54") (name "Net-(U5-PD0{slash}OSCIN)") (class "Default")
      (node (ref "C16") (pin "2") (pinfunction "2_2") (pintype "passive"))
      (node (ref "U5") (pin "5") (pinfunction "PD0/OSCIN_5") (pintype "input"))
      (node (ref "Y1") (pin "2") (pinfunction "OSC2_2") (pintype "passive"))
    )
    (net (code "55") (name "Net-(U5-PD1{slash}OSCOUT)") (class "Default")
      (node (ref "C17") (pin "2") (pinfunction "2_2") (pintype "passive"))
      (node (ref "U5") (pin "6") (pinfunction "PD1/OSCOUT_6") (pintype "output"))
      (node (ref "Y1") (pin "1") (pinfunction "OSC1_1") (pintype "passive"))
    )
    (net (code "56") (name "Net-(U7-CPOUT)") (class "Default")
      (node (ref "C18") (pin "1") (pinfunction "1_1") (pintype "passive"))
      (node (ref "U7") (pin "20") (pinfunction "CPOUT_20") (pintype "passive"))
    )
    (net (code "57") (name "Net-(U7-REGOUT)") (class "Default")
      (node (ref "C21") (pin "1") (pinfunction "1_1") (pintype "passive"))
      (node (ref "U7") (pin "10") (pinfunction "REGOUT_10") (pintype "passive"))
    )
    (net (code "58") (name "Net-(U9-C1)") (class "Default")
      (node (ref "C23") (pin "1") (pinfunction "1_1") (pintype "passive"))
      (node (ref "U9") (pin "10") (pinfunction "C1_10") (pintype "passive"))
    )
    (net (code "59") (name "Net-(U9-SETC)") (class "Default")
      (node (ref "C28") (pin "2") (pinfunction "2_2") (pintype "passive"))
      (node (ref "U9") (pin "12") (pinfunction "SETC_12") (pintype "passive"))
    )
    (net (code "60") (name "Net-(U9-SETP)") (class "Default")
      (node (ref "C28") (pin "1") (pinfunction "1_1") (pintype "passive"))
      (node (ref "U9") (pin "8") (pinfunction "SETP_8") (pintype "passive"))
    )
    (net (code "61") (name "RF3V3") (class "Default")
      (node (ref "*1") (pin "1") (pinfunction "1_1") (pintype "passive"))
      (node (ref "C5") (pin "2") (pinfunction "2_2") (pintype "passive"))
      (node (ref "C8") (pin "1") (pinfunction "1_1") (pintype "passive"))
      (node (ref "R4") (pin "1") (pinfunction "1_1") (pintype "passive"))
      (node (ref "U8") (pin "2") (pinfunction "2_2") (pintype "passive"))
    )
    (net (code "62") (name "VBAT") (class "Default")
      (node (ref "*2") (pin "1") (pinfunction "1_1") (pintype "passive"))
      (node (ref "C7") (pin "1") (pinfunction "1_1") (pintype "passive"))
      (node (ref "R2") (pin "1") (pinfunction "1_1") (pintype "passive"))
      (node (ref "R7") (pin "2") (pinfunction "2_2") (pintype "passive"))
    )
    (net (code "63") (name "VBATIN") (class "Default")
      (node (ref "C2") (pin "2") (pinfunction "2_2") (pintype "passive"))
      (node (ref "CON1") (pin "1") (pinfunction "1_1") (pintype "passive"))
      (node (ref "S1") (pin "1") (pinfunction "1_1") (pintype "passive"))
      (node (ref "U1") (pin "5") (pinfunction "PRAG_5") (pintype "passive"))
    )
    (net (code "64") (name "VGND") (class "Default")
      (node (ref "C1") (pin "1") (pinfunction "1_1") (pintype "passive"))
      (node (ref "C2") (pin "1") (pinfunction "1_1") (pintype "passive"))
      (node (ref "CON1") (pin "2") (pinfunction "2_2") (pintype "passive"))
      (node (ref "R5") (pin "1") (pinfunction "1_1") (pintype "passive"))
      (node (ref "R6") (pin "1") (pinfunction "1_1") (pintype "passive"))
      (node (ref "U1") (pin "2") (pinfunction "Vss_2") (pintype "passive"))
      (node (ref "U2") (pin "5") (pinfunction "5_5") (pintype "power_in"))
    )
    (net (code "65") (name "unconnected-(S1-Pad3)") (class "Default")
      (node (ref "S1") (pin "3") (pinfunction "3_3") (pintype "passive"))
    )
    (net (code "66") (name "unconnected-(U2-Pad3)") (class "Default")
      (node (ref "U2") (pin "3") (pinfunction "3_3") (pintype "power_in"))
    )
    (net (code "67") (name "unconnected-(U5-PA8-Pad29)") (class "Default")
      (node (ref "U5") (pin "29") (pinfunction "PA8_29") (pintype "bidirectional"))
    )
    (net (code "68") (name "unconnected-(U5-PA15{slash}JTDI-Pad38)") (class "Default")
      (node (ref "U5") (pin "38") (pinfunction "PA15/JTDI_38") (pintype "bidirectional"))
    )
    (net (code "69") (name "unconnected-(U5-PB3{slash}JTDO-Pad39)") (class "Default")
      (node (ref "U5") (pin "39") (pinfunction "PB3/JTDO_39") (pintype "bidirectional"))
    )
    (net (code "70") (name "unconnected-(U5-PB4{slash}JNTRST-Pad40)") (class "Default")
      (node (ref "U5") (pin "40") (pinfunction "PB4/JNTRST_40") (pintype "bidirectional"))
    )
    (net (code "71") (name "unconnected-(U5-PC13{slash}RTC-Pad2)") (class "Default")
      (node (ref "U5") (pin "2") (pinfunction "PC13/RTC_2") (pintype "bidirectional"))
    )
    (net (code "72") (name "unconnected-(U5-PC14{slash}OSC32IN-Pad3)") (class "Default")
      (node (ref "U5") (pin "3") (pinfunction "PC14/OSC32IN_3") (pintype "bidirectional"))
    )
    (net (code "73") (name "unconnected-(U5-PC15{slash}OSC32OUT-Pad4)") (class "Default")
      (node (ref "U5") (pin "4") (pinfunction "PC15/OSC32OUT_4") (pintype "bidirectional"))
    )
    (net (code "74") (name "unconnected-(U7-AUX_CL-Pad7)") (class "Default")
      (node (ref "U7") (pin "7") (pinfunction "AUX_CL_7") (pintype "passive"))
    )
    (net (code "75") (name "unconnected-(U7-AUX_DA-Pad6)") (class "Default")
      (node (ref "U7") (pin "6") (pinfunction "AUX_DA_6") (pintype "passive"))
    )
    (net (code "76") (name "unconnected-(U7-CLKOUT-Pad22)") (class "Default")
      (node (ref "U7") (pin "22") (pinfunction "CLKOUT_22") (pintype "passive"))
    )
    (net (code "77") (name "unconnected-(U7-NC-Pad2)") (class "Default")
      (node (ref "U7") (pin "2") (pinfunction "NC_2") (pintype "passive"))
    )
    (net (code "78") (name "unconnected-(U7-NC-Pad3)") (class "Default")
      (node (ref "U7") (pin "3") (pinfunction "NC_3") (pintype "passive"))
    )
    (net (code "79") (name "unconnected-(U7-NC-Pad4)") (class "Default")
      (node (ref "U7") (pin "4") (pinfunction "NC_4") (pintype "passive"))
    )
    (net (code "80") (name "unconnected-(U7-NC-Pad5)") (class "Default")
      (node (ref "U7") (pin "5") (pinfunction "NC_5") (pintype "passive"))
    )
    (net (code "81") (name "unconnected-(U7-NC-Pad14)") (class "Default")
      (node (ref "U7") (pin "14") (pinfunction "NC_14") (pintype "passive"))
    )
    (net (code "82") (name "unconnected-(U7-NC-Pad15)") (class "Default")
      (node (ref "U7") (pin "15") (pinfunction "NC_15") (pintype "passive"))
    )
    (net (code "83") (name "unconnected-(U7-NC-Pad16)") (class "Default")
      (node (ref "U7") (pin "16") (pinfunction "NC_16") (pintype "passive"))
    )
    (net (code "84") (name "unconnected-(U7-NC-Pad17)") (class "Default")
      (node (ref "U7") (pin "17") (pinfunction "NC_17") (pintype "passive"))
    )
    (net (code "85") (name "unconnected-(U7-RESV-Pad19)") (class "Default")
      (node (ref "U7") (pin "19") (pinfunction "RESV_19") (pintype "passive"))
    )
    (net (code "86") (name "unconnected-(U7-RESV-Pad21)") (class "Default")
      (node (ref "U7") (pin "21") (pinfunction "RESV_21") (pintype "passive"))
    )
    (net (code "87") (name "unconnected-(U9-DRDY-Pad15)") (class "Default")
      (node (ref "U9") (pin "15") (pinfunction "DRDY_15") (pintype "passive"))
    )
    (net (code "88") (name "unconnected-(U9-NC-Pad3)") (class "Default")
      (node (ref "U9") (pin "3") (pinfunction "NC_3") (pintype "passive"))
    )
    (net (code "89") (name "unconnected-(U9-NC-Pad5)") (class "Default")
      (node (ref "U9") (pin "5") (pinfunction "NC_5") (pintype "passive"))
    )
    (net (code "90") (name "unconnected-(U9-NC-Pad6)") (class "Default")
      (node (ref "U9") (pin "6") (pinfunction "NC_6") (pintype "passive"))
    )
    (net (code "91") (name "unconnected-(U9-NC-Pad7)") (class "Default")
      (node (ref "U9") (pin "7") (pinfunction "NC_7") (pintype "passive"))
    )
    (net (code "92") (name "unconnected-(U9-NC-Pad14)") (class "Default")
      (node (ref "U9") (pin "14") (pinfunction "NC_14") (pintype "passive"))
    )
    (net (code "93") (name "unconnected-(U10-SDO-Pad6)") (class "Default")
      (node (ref "U10") (pin "6") (pinfunction "SDO_6") (pintype "passive"))
    )
  )
)
